# testLouis.net
KiCad netlist of a schematic drawn in Altium Designer
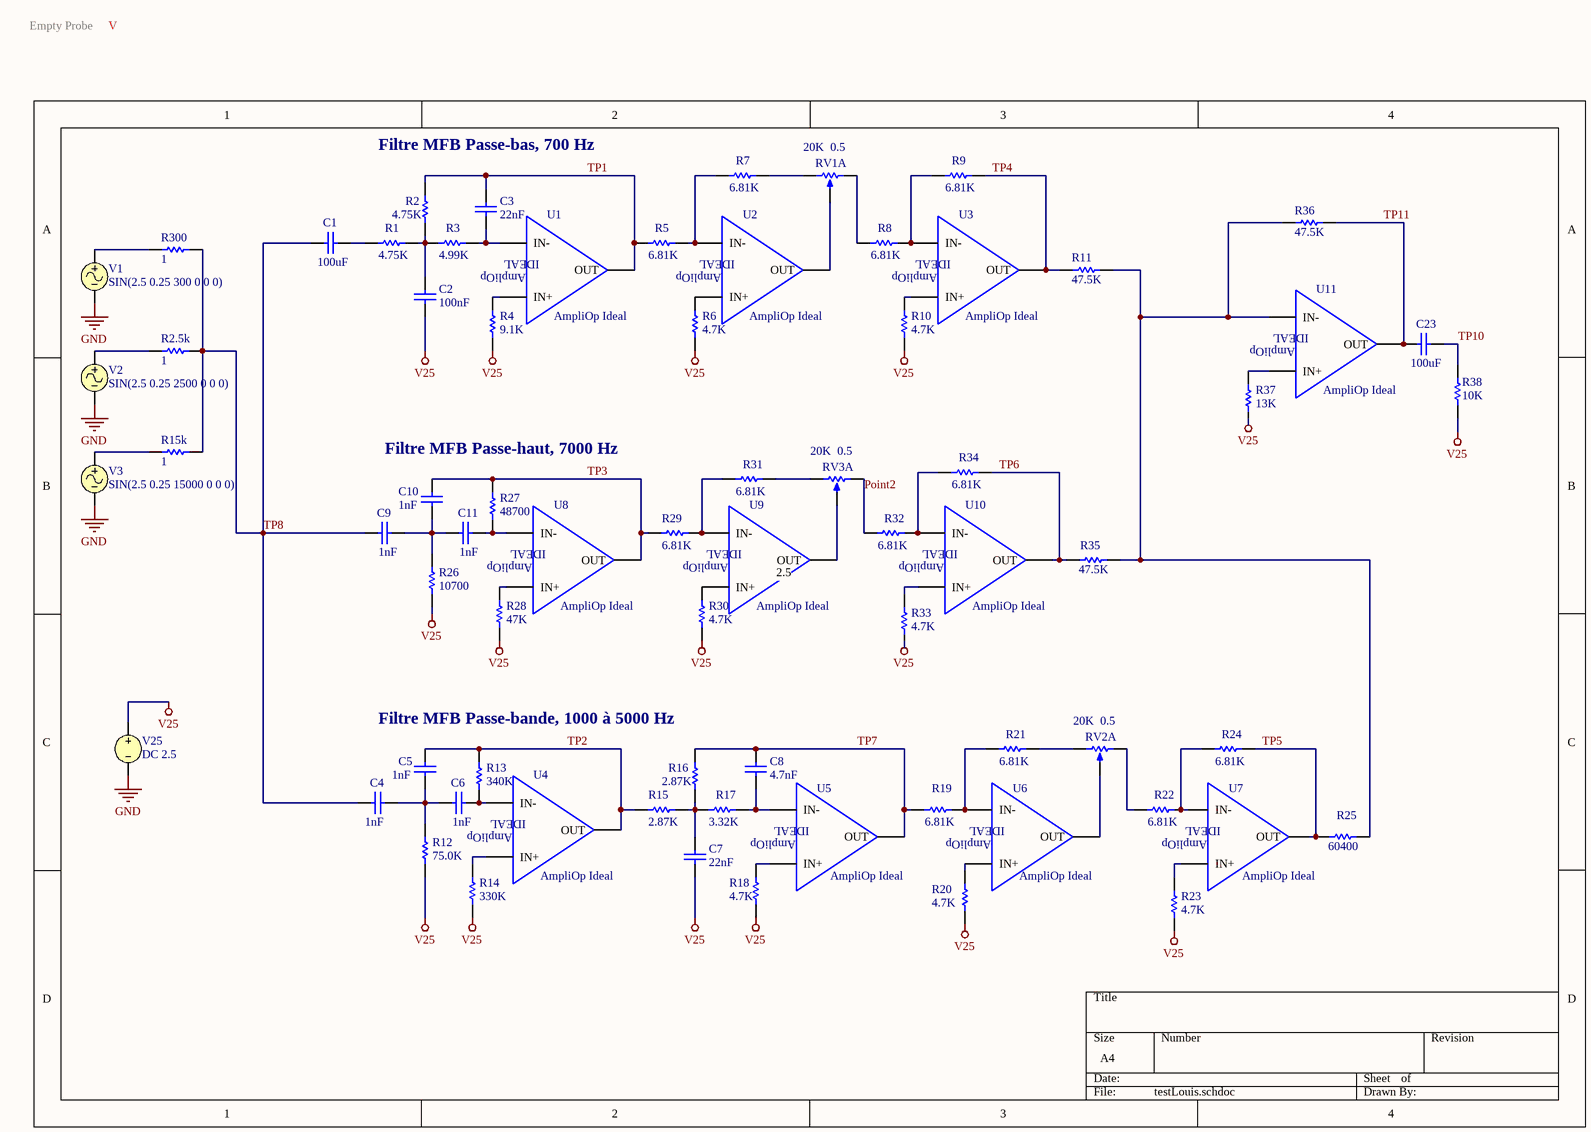
[diagram p0: testLouis.schdoc]

(export (version "E")
  (design (tool "Eeschema 10.0.6"))
  (components
    (comp (ref "C1")
      (value "100uF")
      (footprint "RAD-0.3")
      (description "Capacitor")
      (fields (field (name "Comment") "Cap") (field (name "PUBLISHER") "Altium Limited"))
      (libsource (lib "Miscellaneous Devices") (part "Cap"))
    )
    (comp (ref "C2")
      (value "100nF")
      (footprint "RAD-0.3")
      (description "Capacitor")
      (fields (field (name "Comment") "Cap") (field (name "PUBLISHER") "Altium Limited"))
      (libsource (lib "Miscellaneous Devices") (part "Cap"))
    )
    (comp (ref "C3")
      (value "22nF")
      (footprint "RAD-0.3")
      (description "Capacitor")
      (fields (field (name "Comment") "Cap") (field (name "PUBLISHER") "Altium Limited"))
      (libsource (lib "Miscellaneous Devices") (part "Cap"))
    )
    (comp (ref "C4")
      (value "1nF")
      (footprint "RAD-0.3")
      (description "Capacitor")
      (fields (field (name "Comment") "Cap") (field (name "PUBLISHER") "Altium Limited"))
      (libsource (lib "Miscellaneous Devices") (part "Cap"))
    )
    (comp (ref "C5")
      (value "1nF")
      (footprint "RAD-0.3")
      (description "Capacitor")
      (fields (field (name "Comment") "Cap") (field (name "PUBLISHER") "Altium Limited"))
      (libsource (lib "Miscellaneous Devices") (part "Cap"))
    )
    (comp (ref "C6")
      (value "1nF")
      (footprint "RAD-0.3")
      (description "Capacitor")
      (fields (field (name "Comment") "Cap") (field (name "PUBLISHER") "Altium Limited"))
      (libsource (lib "Miscellaneous Devices") (part "Cap"))
    )
    (comp (ref "C7")
      (value "22nF")
      (footprint "RAD-0.3")
      (description "Capacitor")
      (fields (field (name "Comment") "Cap") (field (name "PUBLISHER") "Altium Limited"))
      (libsource (lib "Miscellaneous Devices") (part "Cap"))
    )
    (comp (ref "C8")
      (value "4.7nF")
      (footprint "RAD-0.3")
      (description "Capacitor")
      (fields (field (name "Comment") "Cap") (field (name "PUBLISHER") "Altium Limited"))
      (libsource (lib "Miscellaneous Devices") (part "Cap"))
    )
    (comp (ref "C9")
      (value "1nF")
      (footprint "RAD-0.3")
      (description "Capacitor")
      (fields (field (name "Comment") "Cap") (field (name "PUBLISHER") "Altium Limited"))
      (libsource (lib "Miscellaneous Devices") (part "Cap"))
    )
    (comp (ref "C10")
      (value "1nF")
      (footprint "RAD-0.3")
      (description "Capacitor")
      (fields (field (name "Comment") "Cap") (field (name "PUBLISHER") "Altium Limited"))
      (libsource (lib "Miscellaneous Devices") (part "Cap"))
    )
    (comp (ref "C11")
      (value "1nF")
      (footprint "RAD-0.3")
      (description "Capacitor")
      (fields (field (name "Comment") "Cap") (field (name "PUBLISHER") "Altium Limited"))
      (libsource (lib "Miscellaneous Devices") (part "Cap"))
    )
    (comp (ref "C23")
      (value "100uF")
      (footprint "RAD-0.3")
      (description "Capacitor")
      (fields (field (name "Comment") "Cap") (field (name "PUBLISHER") "Altium Limited"))
      (libsource (lib "Miscellaneous Devices") (part "Cap"))
    )
    (comp (ref "R1")
      (value "4.75K")
      (footprint "AXIAL-0.3")
      (description "Resistor")
      (fields (field (name "Comment") "Res1") (field (name "PUBLISHER") "Altium Limited"))
      (libsource (lib "Miscellaneous Devices") (part "Res1"))
    )
    (comp (ref "R2")
      (value "4.75K")
      (footprint "AXIAL-0.3")
      (description "Resistor")
      (fields (field (name "Comment") "Res1") (field (name "PUBLISHER") "Altium Limited"))
      (libsource (lib "Miscellaneous Devices") (part "Res1"))
    )
    (comp (ref "R2.5k")
      (value "1")
      (description "Resistor")
      (libsource (lib "Simulation Generic Components") (part "Resistor"))
    )
    (comp (ref "R3")
      (value "4.99K")
      (footprint "AXIAL-0.3")
      (description "Resistor")
      (fields (field (name "Comment") "Res1") (field (name "PUBLISHER") "Altium Limited"))
      (libsource (lib "Miscellaneous Devices") (part "Res1"))
    )
    (comp (ref "R4")
      (value "9.1K")
      (footprint "AXIAL-0.3")
      (description "Resistor")
      (fields (field (name "Comment") "Res1") (field (name "PUBLISHER") "Altium Limited"))
      (libsource (lib "Miscellaneous Devices") (part "Res1"))
    )
    (comp (ref "R5")
      (value "6.81K")
      (footprint "AXIAL-0.3")
      (description "Resistor")
      (fields (field (name "Comment") "Res1") (field (name "PUBLISHER") "Altium Limited"))
      (libsource (lib "Miscellaneous Devices") (part "Res1"))
    )
    (comp (ref "R6")
      (value "4.7K")
      (footprint "AXIAL-0.3")
      (description "Resistor")
      (fields (field (name "Comment") "Res1") (field (name "PUBLISHER") "Altium Limited"))
      (libsource (lib "Miscellaneous Devices") (part "Res1"))
    )
    (comp (ref "R7")
      (value "6.81K")
      (footprint "AXIAL-0.3")
      (description "Resistor")
      (fields (field (name "Comment") "Res1") (field (name "PUBLISHER") "Altium Limited"))
      (libsource (lib "Miscellaneous Devices") (part "Res1"))
    )
    (comp (ref "R8")
      (value "6.81K")
      (footprint "AXIAL-0.3")
      (description "Resistor")
      (fields (field (name "Comment") "Res1") (field (name "PUBLISHER") "Altium Limited"))
      (libsource (lib "Miscellaneous Devices") (part "Res1"))
    )
    (comp (ref "R9")
      (value "6.81K")
      (footprint "AXIAL-0.3")
      (description "Resistor")
      (fields (field (name "Comment") "Res1") (field (name "PUBLISHER") "Altium Limited"))
      (libsource (lib "Miscellaneous Devices") (part "Res1"))
    )
    (comp (ref "R10")
      (value "4.7K")
      (footprint "AXIAL-0.3")
      (description "Resistor")
      (fields (field (name "Comment") "Res1") (field (name "PUBLISHER") "Altium Limited"))
      (libsource (lib "Miscellaneous Devices") (part "Res1"))
    )
    (comp (ref "R11")
      (value "47.5K")
      (footprint "AXIAL-0.3")
      (description "Resistor")
      (fields (field (name "Comment") "Res1") (field (name "PUBLISHER") "Altium Limited"))
      (libsource (lib "Miscellaneous Devices") (part "Res1"))
    )
    (comp (ref "R12")
      (value "75.0K")
      (footprint "AXIAL-0.3")
      (description "Resistor")
      (fields (field (name "Comment") "Res1") (field (name "PUBLISHER") "Altium Limited"))
      (libsource (lib "Miscellaneous Devices") (part "Res1"))
    )
    (comp (ref "R13")
      (value "340K")
      (footprint "AXIAL-0.3")
      (description "Resistor")
      (fields (field (name "Comment") "Res1") (field (name "PUBLISHER") "Altium Limited"))
      (libsource (lib "Miscellaneous Devices") (part "Res1"))
    )
    (comp (ref "R14")
      (value "330K")
      (footprint "AXIAL-0.3")
      (description "Resistor")
      (fields (field (name "Comment") "Res1") (field (name "PUBLISHER") "Altium Limited"))
      (libsource (lib "Miscellaneous Devices") (part "Res1"))
    )
    (comp (ref "R15")
      (value "2.87K")
      (footprint "AXIAL-0.3")
      (description "Resistor")
      (fields (field (name "Comment") "Res1") (field (name "PUBLISHER") "Altium Limited"))
      (libsource (lib "Miscellaneous Devices") (part "Res1"))
    )
    (comp (ref "R15k")
      (value "1")
      (description "Resistor")
      (libsource (lib "Simulation Generic Components") (part "Resistor"))
    )
    (comp (ref "R16")
      (value "2.87K")
      (footprint "AXIAL-0.3")
      (description "Resistor")
      (fields (field (name "Comment") "Res1") (field (name "PUBLISHER") "Altium Limited"))
      (libsource (lib "Miscellaneous Devices") (part "Res1"))
    )
    (comp (ref "R17")
      (value "3.32K")
      (footprint "AXIAL-0.3")
      (description "Resistor")
      (fields (field (name "Comment") "Res1") (field (name "PUBLISHER") "Altium Limited"))
      (libsource (lib "Miscellaneous Devices") (part "Res1"))
    )
    (comp (ref "R18")
      (value "4.7K")
      (footprint "AXIAL-0.3")
      (description "Resistor")
      (fields (field (name "Comment") "Res1") (field (name "PUBLISHER") "Altium Limited"))
      (libsource (lib "Miscellaneous Devices") (part "Res1"))
    )
    (comp (ref "R19")
      (value "6.81K")
      (footprint "AXIAL-0.3")
      (description "Resistor")
      (fields (field (name "Comment") "Res1") (field (name "PUBLISHER") "Altium Limited"))
      (libsource (lib "Miscellaneous Devices") (part "Res1"))
    )
    (comp (ref "R20")
      (value "4.7K")
      (footprint "AXIAL-0.3")
      (description "Resistor")
      (fields (field (name "Comment") "Res1") (field (name "PUBLISHER") "Altium Limited"))
      (libsource (lib "Miscellaneous Devices") (part "Res1"))
    )
    (comp (ref "R21")
      (value "6.81K")
      (footprint "AXIAL-0.3")
      (description "Resistor")
      (fields (field (name "Comment") "Res1") (field (name "PUBLISHER") "Altium Limited"))
      (libsource (lib "Miscellaneous Devices") (part "Res1"))
    )
    (comp (ref "R22")
      (value "6.81K")
      (footprint "AXIAL-0.3")
      (description "Resistor")
      (fields (field (name "Comment") "Res1") (field (name "PUBLISHER") "Altium Limited"))
      (libsource (lib "Miscellaneous Devices") (part "Res1"))
    )
    (comp (ref "R23")
      (value "4.7K")
      (footprint "AXIAL-0.3")
      (description "Resistor")
      (fields (field (name "Comment") "Res1") (field (name "PUBLISHER") "Altium Limited"))
      (libsource (lib "Miscellaneous Devices") (part "Res1"))
    )
    (comp (ref "R24")
      (value "6.81K")
      (footprint "AXIAL-0.3")
      (description "Resistor")
      (fields (field (name "Comment") "Res1") (field (name "PUBLISHER") "Altium Limited"))
      (libsource (lib "Miscellaneous Devices") (part "Res1"))
    )
    (comp (ref "R25")
      (value "60400")
      (footprint "AXIAL-0.3")
      (description "Resistor")
      (fields (field (name "Comment") "Res1") (field (name "PUBLISHER") "Altium Limited"))
      (libsource (lib "Miscellaneous Devices") (part "Res1"))
    )
    (comp (ref "R26")
      (value "10700")
      (footprint "AXIAL-0.3")
      (description "Resistor")
      (fields (field (name "Comment") "Res1") (field (name "PUBLISHER") "Altium Limited"))
      (libsource (lib "Miscellaneous Devices") (part "Res1"))
    )
    (comp (ref "R27")
      (value "48700")
      (footprint "AXIAL-0.3")
      (description "Resistor")
      (fields (field (name "Comment") "Res1") (field (name "PUBLISHER") "Altium Limited"))
      (libsource (lib "Miscellaneous Devices") (part "Res1"))
    )
    (comp (ref "R28")
      (value "47K")
      (footprint "AXIAL-0.3")
      (description "Resistor")
      (fields (field (name "Comment") "Res1") (field (name "PUBLISHER") "Altium Limited"))
      (libsource (lib "Miscellaneous Devices") (part "Res1"))
    )
    (comp (ref "R29")
      (value "6.81K")
      (footprint "AXIAL-0.3")
      (description "Resistor")
      (fields (field (name "Comment") "Res1") (field (name "PUBLISHER") "Altium Limited"))
      (libsource (lib "Miscellaneous Devices") (part "Res1"))
    )
    (comp (ref "R30")
      (value "4.7K")
      (footprint "AXIAL-0.3")
      (description "Resistor")
      (fields (field (name "Comment") "Res1") (field (name "PUBLISHER") "Altium Limited"))
      (libsource (lib "Miscellaneous Devices") (part "Res1"))
    )
    (comp (ref "R31")
      (value "6.81K")
      (footprint "AXIAL-0.3")
      (description "Resistor")
      (fields (field (name "Comment") "Res1") (field (name "PUBLISHER") "Altium Limited"))
      (libsource (lib "Miscellaneous Devices") (part "Res1"))
    )
    (comp (ref "R32")
      (value "6.81K")
      (footprint "AXIAL-0.3")
      (description "Resistor")
      (fields (field (name "Comment") "Res1") (field (name "PUBLISHER") "Altium Limited"))
      (libsource (lib "Miscellaneous Devices") (part "Res1"))
    )
    (comp (ref "R33")
      (value "4.7K")
      (footprint "AXIAL-0.3")
      (description "Resistor")
      (fields (field (name "Comment") "Res1") (field (name "PUBLISHER") "Altium Limited"))
      (libsource (lib "Miscellaneous Devices") (part "Res1"))
    )
    (comp (ref "R34")
      (value "6.81K")
      (footprint "AXIAL-0.3")
      (description "Resistor")
      (fields (field (name "Comment") "Res1") (field (name "PUBLISHER") "Altium Limited"))
      (libsource (lib "Miscellaneous Devices") (part "Res1"))
    )
    (comp (ref "R35")
      (value "47.5K")
      (footprint "AXIAL-0.3")
      (description "Resistor")
      (fields (field (name "Comment") "Res1") (field (name "PUBLISHER") "Altium Limited"))
      (libsource (lib "Miscellaneous Devices") (part "Res1"))
    )
    (comp (ref "R36")
      (value "47.5K")
      (footprint "AXIAL-0.3")
      (description "Resistor")
      (fields (field (name "Comment") "Res1") (field (name "PUBLISHER") "Altium Limited"))
      (libsource (lib "Miscellaneous Devices") (part "Res1"))
    )
    (comp (ref "R37")
      (value "13K")
      (footprint "AXIAL-0.3")
      (description "Resistor")
      (fields (field (name "Comment") "Res1") (field (name "PUBLISHER") "Altium Limited"))
      (libsource (lib "Miscellaneous Devices") (part "Res1"))
    )
    (comp (ref "R38")
      (value "10K")
      (footprint "AXIAL-0.3")
      (description "Resistor")
      (fields (field (name "Comment") "Res1") (field (name "PUBLISHER") "Altium Limited"))
      (libsource (lib "Miscellaneous Devices") (part "Res1"))
    )
    (comp (ref "R300")
      (value "1")
      (description "Resistor")
      (libsource (lib "Simulation Generic Components") (part "Resistor"))
    )
    (comp (ref "RV1A")
      (value "20K")
      (footprint "VR5")
      (description "Potentiometer")
      (fields
        (field (name "SET POSITION") "0.5")
        (field (name "Comment") "RPot")
        (field (name "PUBLISHER") "Altium Limited")
      )
      (libsource (lib "Miscellaneous Devices") (part "RPot"))
    )
    (comp (ref "RV2A")
      (value "20K")
      (footprint "VR5")
      (description "Potentiometer")
      (fields
        (field (name "SET POSITION") "0.5")
        (field (name "Comment") "RPot")
        (field (name "PUBLISHER") "Altium Limited")
      )
      (libsource (lib "Miscellaneous Devices") (part "RPot"))
    )
    (comp (ref "RV3A")
      (value "20K")
      (footprint "VR5")
      (description "Potentiometer")
      (fields
        (field (name "SET POSITION") "0.5")
        (field (name "Comment") "RPot")
        (field (name "PUBLISHER") "Altium Limited")
      )
      (libsource (lib "Miscellaneous Devices") (part "RPot"))
    )
    (comp (ref "U1") (value "AmpliOp Ideal") (libsource (lib "Librarie_S2") (part "AmpliOp_ideal")))
    (comp (ref "U2") (value "AmpliOp Ideal") (libsource (lib "Librarie_S2") (part "AmpliOp_ideal")))
    (comp (ref "U3") (value "AmpliOp Ideal") (libsource (lib "Librarie_S2") (part "AmpliOp_ideal")))
    (comp (ref "U4") (value "AmpliOp Ideal") (libsource (lib "Librarie_S2") (part "AmpliOp_ideal")))
    (comp (ref "U5") (value "AmpliOp Ideal") (libsource (lib "Librarie_S2") (part "AmpliOp_ideal")))
    (comp (ref "U6") (value "AmpliOp Ideal") (libsource (lib "Librarie_S2") (part "AmpliOp_ideal")))
    (comp (ref "U7") (value "AmpliOp Ideal") (libsource (lib "Librarie_S2") (part "AmpliOp_ideal")))
    (comp (ref "U8") (value "AmpliOp Ideal") (libsource (lib "Librarie_S2") (part "AmpliOp_ideal")))
    (comp (ref "U9") (value "AmpliOp Ideal") (libsource (lib "Librarie_S2") (part "AmpliOp_ideal")))
    (comp (ref "U10") (value "AmpliOp Ideal") (libsource (lib "Librarie_S2") (part "AmpliOp_ideal")))
    (comp (ref "U11") (value "AmpliOp Ideal") (libsource (lib "Librarie_S2") (part "AmpliOp_ideal")))
    (comp (ref "V1")
      (value "SIN(2.5 0.25 300 0 0 0)")
      (description "Sinusoidal Voltage Source")
      (fields (field (name "PUBLISHER") "Altium Limited"))
      (libsource (lib "Simulation Sources") (part "VSIN"))
    )
    (comp (ref "V2")
      (value "SIN(2.5 0.25 2500 0 0 0)")
      (description "Sinusoidal Voltage Source")
      (fields (field (name "PUBLISHER") "Altium Limited"))
      (libsource (lib "Simulation Sources") (part "VSIN"))
    )
    (comp (ref "V3")
      (value "SIN(2.5 0.25 15000 0 0 0)")
      (description "Sinusoidal Voltage Source")
      (fields (field (name "PUBLISHER") "Altium Limited"))
      (libsource (lib "Simulation Sources") (part "VSIN"))
    )
    (comp (ref "V25")
      (value "DC 2.5")
      (description "Voltage Source")
      (fields (field (name "PUBLISHER") "Altium Limited"))
      (libsource (lib "Simulation Generic Components") (part "VSRC"))
    )
  )
  (nets
    (net (code "1") (name "/Point2") (class "Default")
      (node (ref "R32") (pin "1") (pinfunction "1_1") (pintype "passive"))
      (node (ref "RV3A") (pin "2") (pinfunction "BOT_2") (pintype "passive"))
    )
    (net (code "2") (name "/TP1") (class "Default")
      (node (ref "C3") (pin "1") (pinfunction "1_1") (pintype "passive"))
      (node (ref "R2") (pin "1") (pinfunction "1_1") (pintype "passive"))
      (node (ref "R5") (pin "1") (pinfunction "1_1") (pintype "passive"))
      (node (ref "U1") (pin "3") (pinfunction "OUT_3") (pintype "passive"))
    )
    (net (code "3") (name "/TP2") (class "Default")
      (node (ref "C5") (pin "1") (pinfunction "1_1") (pintype "passive"))
      (node (ref "R13") (pin "1") (pinfunction "1_1") (pintype "passive"))
      (node (ref "R15") (pin "1") (pinfunction "1_1") (pintype "passive"))
      (node (ref "U4") (pin "3") (pinfunction "OUT_3") (pintype "passive"))
    )
    (net (code "4") (name "/TP3") (class "Default")
      (node (ref "C10") (pin "1") (pinfunction "1_1") (pintype "passive"))
      (node (ref "R27") (pin "1") (pinfunction "1_1") (pintype "passive"))
      (node (ref "R29") (pin "1") (pinfunction "1_1") (pintype "passive"))
      (node (ref "U8") (pin "3") (pinfunction "OUT_3") (pintype "passive"))
    )
    (net (code "5") (name "/TP4") (class "Default")
      (node (ref "R11") (pin "1") (pinfunction "1_1") (pintype "passive"))
      (node (ref "R9") (pin "2") (pinfunction "2_2") (pintype "passive"))
      (node (ref "U3") (pin "3") (pinfunction "OUT_3") (pintype "passive"))
    )
    (net (code "6") (name "/TP5") (class "Default")
      (node (ref "R24") (pin "2") (pinfunction "2_2") (pintype "passive"))
      (node (ref "R25") (pin "1") (pinfunction "1_1") (pintype "passive"))
      (node (ref "U7") (pin "3") (pinfunction "OUT_3") (pintype "passive"))
    )
    (net (code "7") (name "/TP6") (class "Default")
      (node (ref "R34") (pin "2") (pinfunction "2_2") (pintype "passive"))
      (node (ref "R35") (pin "1") (pinfunction "1_1") (pintype "passive"))
      (node (ref "U10") (pin "3") (pinfunction "OUT_3") (pintype "passive"))
    )
    (net (code "8") (name "/TP7") (class "Default")
      (node (ref "C8") (pin "1") (pinfunction "1_1") (pintype "passive"))
      (node (ref "R16") (pin "1") (pinfunction "1_1") (pintype "passive"))
      (node (ref "R19") (pin "1") (pinfunction "1_1") (pintype "passive"))
      (node (ref "U5") (pin "3") (pinfunction "OUT_3") (pintype "passive"))
    )
    (net (code "9") (name "/TP8") (class "Default")
      (node (ref "C1") (pin "1") (pinfunction "1_1") (pintype "passive"))
      (node (ref "C4") (pin "1") (pinfunction "1_1") (pintype "passive"))
      (node (ref "C9") (pin "1") (pinfunction "1_1") (pintype "passive"))
      (node (ref "R15k") (pin "2") (pinfunction "2_2") (pintype "passive"))
      (node (ref "R2.5k") (pin "2") (pinfunction "2_2") (pintype "passive"))
      (node (ref "R300") (pin "2") (pinfunction "2_2") (pintype "passive"))
    )
    (net (code "10") (name "/TP10") (class "Default")
      (node (ref "C23") (pin "2") (pinfunction "2_2") (pintype "passive"))
      (node (ref "R38") (pin "2") (pinfunction "2_2") (pintype "passive"))
    )
    (net (code "11") (name "/TP11") (class "Default")
      (node (ref "C23") (pin "1") (pinfunction "1_1") (pintype "passive"))
      (node (ref "R36") (pin "2") (pinfunction "2_2") (pintype "passive"))
      (node (ref "U11") (pin "3") (pinfunction "OUT_3") (pintype "passive"))
    )
    (net (code "12") (name "GND") (class "Default")
      (node (ref "V1") (pin "2") (pinfunction "2_2") (pintype "passive"))
      (node (ref "V2") (pin "2") (pinfunction "2_2") (pintype "passive"))
      (node (ref "V25") (pin "2") (pinfunction "2_2") (pintype "passive"))
      (node (ref "V3") (pin "2") (pinfunction "2_2") (pintype "passive"))
    )
    (net (code "13") (name "Net-(C1-Pad2)") (class "Default")
      (node (ref "C1") (pin "2") (pinfunction "2_2") (pintype "passive"))
      (node (ref "R1") (pin "1") (pinfunction "1_1") (pintype "passive"))
    )
    (net (code "14") (name "Net-(C2-Pad1)") (class "Default")
      (node (ref "C2") (pin "1") (pinfunction "1_1") (pintype "passive"))
      (node (ref "R1") (pin "2") (pinfunction "2_2") (pintype "passive"))
      (node (ref "R2") (pin "2") (pinfunction "2_2") (pintype "passive"))
      (node (ref "R3") (pin "1") (pinfunction "1_1") (pintype "passive"))
    )
    (net (code "15") (name "Net-(C4-Pad2)") (class "Default")
      (node (ref "C4") (pin "2") (pinfunction "2_2") (pintype "passive"))
      (node (ref "C5") (pin "2") (pinfunction "2_2") (pintype "passive"))
      (node (ref "C6") (pin "1") (pinfunction "1_1") (pintype "passive"))
      (node (ref "R12") (pin "1") (pinfunction "1_1") (pintype "passive"))
    )
    (net (code "16") (name "Net-(C7-Pad1)") (class "Default")
      (node (ref "C7") (pin "1") (pinfunction "1_1") (pintype "passive"))
      (node (ref "R15") (pin "2") (pinfunction "2_2") (pintype "passive"))
      (node (ref "R16") (pin "2") (pinfunction "2_2") (pintype "passive"))
      (node (ref "R17") (pin "1") (pinfunction "1_1") (pintype "passive"))
    )
    (net (code "17") (name "Net-(C10-Pad2)") (class "Default")
      (node (ref "C10") (pin "2") (pinfunction "2_2") (pintype "passive"))
      (node (ref "C11") (pin "1") (pinfunction "1_1") (pintype "passive"))
      (node (ref "C9") (pin "2") (pinfunction "2_2") (pintype "passive"))
      (node (ref "R26") (pin "1") (pinfunction "1_1") (pintype "passive"))
    )
    (net (code "18") (name "Net-(R2.5k-Pad1)") (class "Default")
      (node (ref "R2.5k") (pin "1") (pinfunction "1_1") (pintype "passive"))
      (node (ref "V2") (pin "1") (pinfunction "1_1") (pintype "passive"))
    )
    (net (code "19") (name "Net-(R15k-Pad1)") (class "Default")
      (node (ref "R15k") (pin "1") (pinfunction "1_1") (pintype "passive"))
      (node (ref "V3") (pin "1") (pinfunction "1_1") (pintype "passive"))
    )
    (net (code "20") (name "Net-(R300-Pad1)") (class "Default")
      (node (ref "R300") (pin "1") (pinfunction "1_1") (pintype "passive"))
      (node (ref "V1") (pin "1") (pinfunction "1_1") (pintype "passive"))
    )
    (net (code "21") (name "Net-(RV1A-BOT)") (class "Default")
      (node (ref "R8") (pin "1") (pinfunction "1_1") (pintype "passive"))
      (node (ref "RV1A") (pin "2") (pinfunction "BOT_2") (pintype "passive"))
    )
    (net (code "22") (name "Net-(RV1A-TAP)") (class "Default")
      (node (ref "RV1A") (pin "3") (pinfunction "TAP_3") (pintype "passive"))
      (node (ref "U2") (pin "3") (pinfunction "OUT_3") (pintype "passive"))
    )
    (net (code "23") (name "Net-(RV1A-TOP)") (class "Default")
      (node (ref "R7") (pin "2") (pinfunction "2_2") (pintype "passive"))
      (node (ref "RV1A") (pin "1") (pinfunction "TOP_1") (pintype "passive"))
    )
    (net (code "24") (name "Net-(RV2A-BOT)") (class "Default")
      (node (ref "R22") (pin "1") (pinfunction "1_1") (pintype "passive"))
      (node (ref "RV2A") (pin "2") (pinfunction "BOT_2") (pintype "passive"))
    )
    (net (code "25") (name "Net-(RV2A-TAP)") (class "Default")
      (node (ref "RV2A") (pin "3") (pinfunction "TAP_3") (pintype "passive"))
      (node (ref "U6") (pin "3") (pinfunction "OUT_3") (pintype "passive"))
    )
    (net (code "26") (name "Net-(RV2A-TOP)") (class "Default")
      (node (ref "R21") (pin "2") (pinfunction "2_2") (pintype "passive"))
      (node (ref "RV2A") (pin "1") (pinfunction "TOP_1") (pintype "passive"))
    )
    (net (code "27") (name "Net-(RV3A-TAP)") (class "Default")
      (node (ref "RV3A") (pin "3") (pinfunction "TAP_3") (pintype "passive"))
      (node (ref "U9") (pin "3") (pinfunction "OUT_3") (pintype "passive"))
    )
    (net (code "28") (name "Net-(RV3A-TOP)") (class "Default")
      (node (ref "R31") (pin "2") (pinfunction "2_2") (pintype "passive"))
      (node (ref "RV3A") (pin "1") (pinfunction "TOP_1") (pintype "passive"))
    )
    (net (code "29") (name "Net-(U1-IN+)") (class "Default")
      (node (ref "R4") (pin "1") (pinfunction "1_1") (pintype "passive"))
      (node (ref "U1") (pin "1") (pinfunction "IN+_1") (pintype "passive"))
    )
    (net (code "30") (name "Net-(U1-IN-)") (class "Default")
      (node (ref "C3") (pin "2") (pinfunction "2_2") (pintype "passive"))
      (node (ref "R3") (pin "2") (pinfunction "2_2") (pintype "passive"))
      (node (ref "U1") (pin "2") (pinfunction "IN-_2") (pintype "passive"))
    )
    (net (code "31") (name "Net-(U2-IN+)") (class "Default")
      (node (ref "R6") (pin "1") (pinfunction "1_1") (pintype "passive"))
      (node (ref "U2") (pin "1") (pinfunction "IN+_1") (pintype "passive"))
    )
    (net (code "32") (name "Net-(U2-IN-)") (class "Default")
      (node (ref "R5") (pin "2") (pinfunction "2_2") (pintype "passive"))
      (node (ref "R7") (pin "1") (pinfunction "1_1") (pintype "passive"))
      (node (ref "U2") (pin "2") (pinfunction "IN-_2") (pintype "passive"))
    )
    (net (code "33") (name "Net-(U3-IN+)") (class "Default")
      (node (ref "R10") (pin "1") (pinfunction "1_1") (pintype "passive"))
      (node (ref "U3") (pin "1") (pinfunction "IN+_1") (pintype "passive"))
    )
    (net (code "34") (name "Net-(U3-IN-)") (class "Default")
      (node (ref "R8") (pin "2") (pinfunction "2_2") (pintype "passive"))
      (node (ref "R9") (pin "1") (pinfunction "1_1") (pintype "passive"))
      (node (ref "U3") (pin "2") (pinfunction "IN-_2") (pintype "passive"))
    )
    (net (code "35") (name "Net-(U4-IN+)") (class "Default")
      (node (ref "R14") (pin "1") (pinfunction "1_1") (pintype "passive"))
      (node (ref "U4") (pin "1") (pinfunction "IN+_1") (pintype "passive"))
    )
    (net (code "36") (name "Net-(U4-IN-)") (class "Default")
      (node (ref "C6") (pin "2") (pinfunction "2_2") (pintype "passive"))
      (node (ref "R13") (pin "2") (pinfunction "2_2") (pintype "passive"))
      (node (ref "U4") (pin "2") (pinfunction "IN-_2") (pintype "passive"))
    )
    (net (code "37") (name "Net-(U5-IN+)") (class "Default")
      (node (ref "R18") (pin "1") (pinfunction "1_1") (pintype "passive"))
      (node (ref "U5") (pin "1") (pinfunction "IN+_1") (pintype "passive"))
    )
    (net (code "38") (name "Net-(U5-IN-)") (class "Default")
      (node (ref "C8") (pin "2") (pinfunction "2_2") (pintype "passive"))
      (node (ref "R17") (pin "2") (pinfunction "2_2") (pintype "passive"))
      (node (ref "U5") (pin "2") (pinfunction "IN-_2") (pintype "passive"))
    )
    (net (code "39") (name "Net-(U6-IN+)") (class "Default")
      (node (ref "R20") (pin "1") (pinfunction "1_1") (pintype "passive"))
      (node (ref "U6") (pin "1") (pinfunction "IN+_1") (pintype "passive"))
    )
    (net (code "40") (name "Net-(U6-IN-)") (class "Default")
      (node (ref "R19") (pin "2") (pinfunction "2_2") (pintype "passive"))
      (node (ref "R21") (pin "1") (pinfunction "1_1") (pintype "passive"))
      (node (ref "U6") (pin "2") (pinfunction "IN-_2") (pintype "passive"))
    )
    (net (code "41") (name "Net-(U7-IN+)") (class "Default")
      (node (ref "R23") (pin "1") (pinfunction "1_1") (pintype "passive"))
      (node (ref "U7") (pin "1") (pinfunction "IN+_1") (pintype "passive"))
    )
    (net (code "42") (name "Net-(U7-IN-)") (class "Default")
      (node (ref "R22") (pin "2") (pinfunction "2_2") (pintype "passive"))
      (node (ref "R24") (pin "1") (pinfunction "1_1") (pintype "passive"))
      (node (ref "U7") (pin "2") (pinfunction "IN-_2") (pintype "passive"))
    )
    (net (code "43") (name "Net-(U8-IN+)") (class "Default")
      (node (ref "R28") (pin "1") (pinfunction "1_1") (pintype "passive"))
      (node (ref "U8") (pin "1") (pinfunction "IN+_1") (pintype "passive"))
    )
    (net (code "44") (name "Net-(U8-IN-)") (class "Default")
      (node (ref "C11") (pin "2") (pinfunction "2_2") (pintype "passive"))
      (node (ref "R27") (pin "2") (pinfunction "2_2") (pintype "passive"))
      (node (ref "U8") (pin "2") (pinfunction "IN-_2") (pintype "passive"))
    )
    (net (code "45") (name "Net-(U9-IN+)") (class "Default")
      (node (ref "R30") (pin "1") (pinfunction "1_1") (pintype "passive"))
      (node (ref "U9") (pin "1") (pinfunction "IN+_1") (pintype "passive"))
    )
    (net (code "46") (name "Net-(U9-IN-)") (class "Default")
      (node (ref "R29") (pin "2") (pinfunction "2_2") (pintype "passive"))
      (node (ref "R31") (pin "1") (pinfunction "1_1") (pintype "passive"))
      (node (ref "U9") (pin "2") (pinfunction "IN-_2") (pintype "passive"))
    )
    (net (code "47") (name "Net-(U10-IN+)") (class "Default")
      (node (ref "R33") (pin "1") (pinfunction "1_1") (pintype "passive"))
      (node (ref "U10") (pin "1") (pinfunction "IN+_1") (pintype "passive"))
    )
    (net (code "48") (name "Net-(U10-IN-)") (class "Default")
      (node (ref "R32") (pin "2") (pinfunction "2_2") (pintype "passive"))
      (node (ref "R34") (pin "1") (pinfunction "1_1") (pintype "passive"))
      (node (ref "U10") (pin "2") (pinfunction "IN-_2") (pintype "passive"))
    )
    (net (code "49") (name "Net-(U11-IN+)") (class "Default")
      (node (ref "R37") (pin "1") (pinfunction "1_1") (pintype "passive"))
      (node (ref "U11") (pin "1") (pinfunction "IN+_1") (pintype "passive"))
    )
    (net (code "50") (name "Net-(U11-IN-)") (class "Default")
      (node (ref "R11") (pin "2") (pinfunction "2_2") (pintype "passive"))
      (node (ref "R25") (pin "2") (pinfunction "2_2") (pintype "passive"))
      (node (ref "R35") (pin "2") (pinfunction "2_2") (pintype "passive"))
      (node (ref "R36") (pin "1") (pinfunction "1_1") (pintype "passive"))
      (node (ref "U11") (pin "2") (pinfunction "IN-_2") (pintype "passive"))
    )
    (net (code "51") (name "V25") (class "Default")
      (node (ref "C2") (pin "2") (pinfunction "2_2") (pintype "passive"))
      (node (ref "C7") (pin "2") (pinfunction "2_2") (pintype "passive"))
      (node (ref "R10") (pin "2") (pinfunction "2_2") (pintype "passive"))
      (node (ref "R12") (pin "2") (pinfunction "2_2") (pintype "passive"))
      (node (ref "R14") (pin "2") (pinfunction "2_2") (pintype "passive"))
      (node (ref "R18") (pin "2") (pinfunction "2_2") (pintype "passive"))
      (node (ref "R20") (pin "2") (pinfunction "2_2") (pintype "passive"))
      (node (ref "R23") (pin "2") (pinfunction "2_2") (pintype "passive"))
      (node (ref "R26") (pin "2") (pinfunction "2_2") (pintype "passive"))
      (node (ref "R28") (pin "2") (pinfunction "2_2") (pintype "passive"))
      (node (ref "R30") (pin "2") (pinfunction "2_2") (pintype "passive"))
      (node (ref "R33") (pin "2") (pinfunction "2_2") (pintype "passive"))
      (node (ref "R37") (pin "2") (pinfunction "2_2") (pintype "passive"))
      (node (ref "R38") (pin "1") (pinfunction "1_1") (pintype "passive"))
      (node (ref "R4") (pin "2") (pinfunction "2_2") (pintype "passive"))
      (node (ref "R6") (pin "2") (pinfunction "2_2") (pintype "passive"))
      (node (ref "V25") (pin "1") (pinfunction "1_1") (pintype "passive"))
    )
  )
)
